# Module.net
KiCad netlist of a schematic drawn in Altium Designer
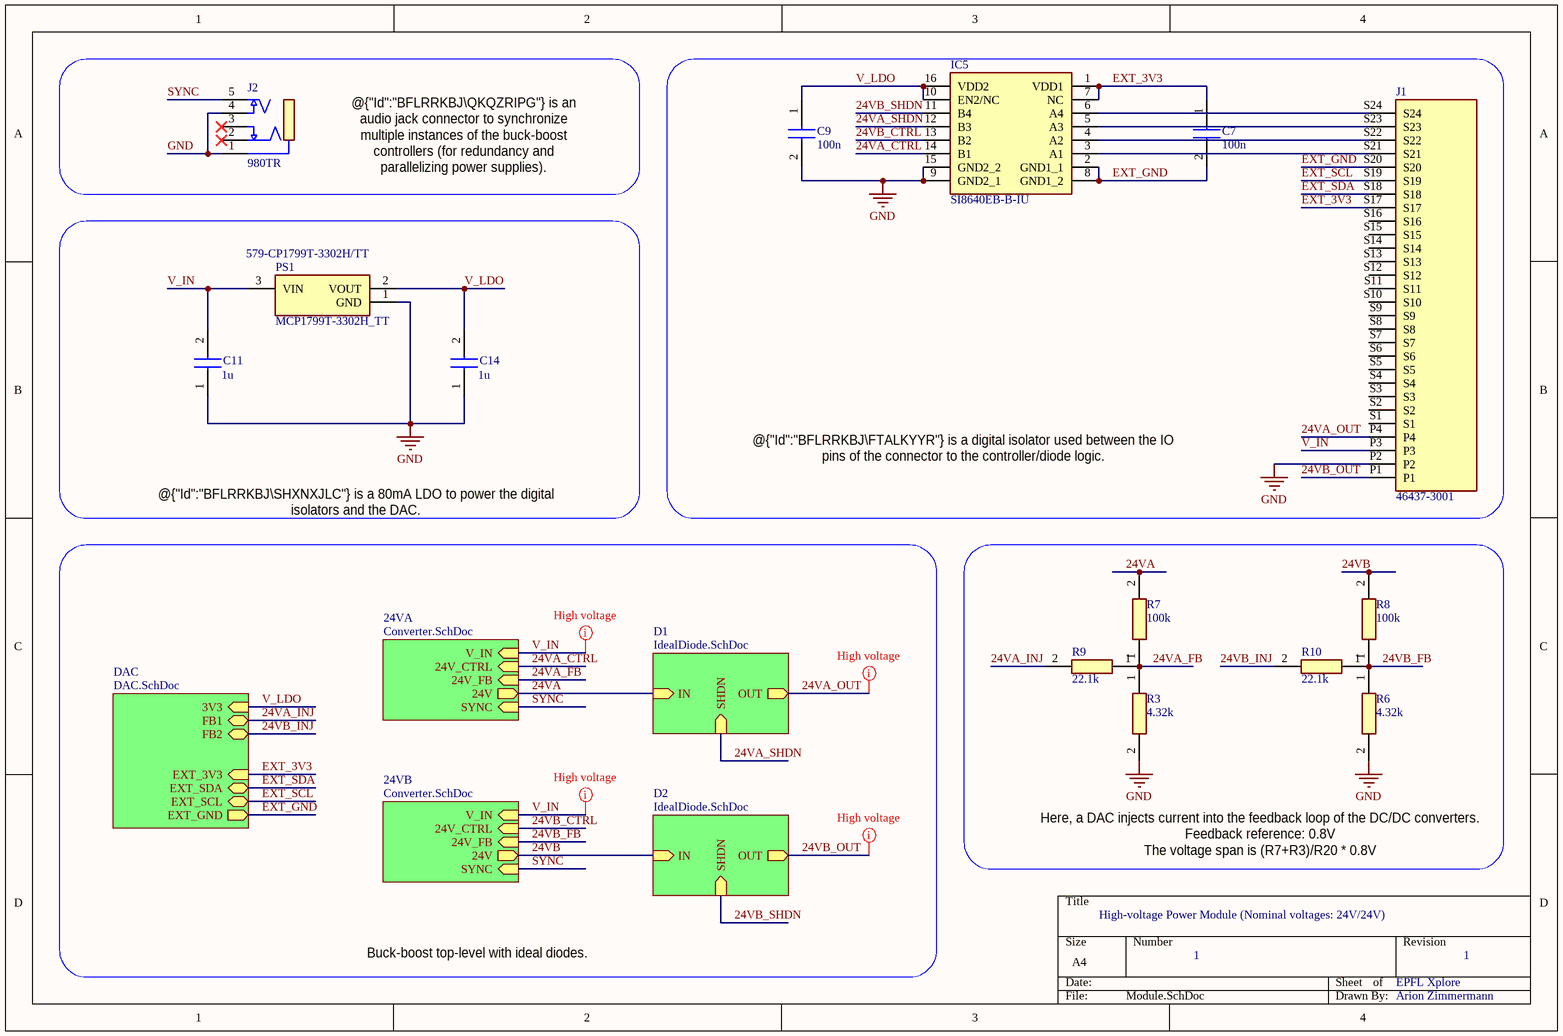
[diagram p0: Module.SchDoc]

(export (version "E")
  (design (tool "Eeschema 10.0.6"))
  (components
    (comp (ref "C7")
      (value "100n")
      (footprint "CAPC1608X95N")
      (description "Capacitor")
      (fields
        (field (name "MANUFACTURER_PART_NUMBER") "C0603C104K5RACTU")
        (field (name "MOUSER PART NUMBER") "80-C0603C104K5R")
      )
      (libsource (lib "*") (part "C0603C104K5RACTU"))
    )
    (comp (ref "C9")
      (value "100n")
      (footprint "CAPC1608X95N")
      (description "Capacitor")
      (fields
        (field (name "MANUFACTURER_PART_NUMBER") "C0603C104K5RACTU")
        (field (name "MOUSER PART NUMBER") "80-C0603C104K5R")
      )
      (libsource (lib "*") (part "C0603C104K5RACTU"))
    )
    (comp (ref "C11")
      (value "1u")
      (footprint "CAPC3216X110N")
      (description "Capacitor")
      (fields
        (field (name "MANUFACTURER_PART_NUMBER") "C1206C105K5RAC")
        (field (name "MOUSER PART NUMBER") "80-C1206C105K5RAC")
      )
      (libsource (lib "*") (part "C1206C105K5RAC"))
    )
    (comp (ref "C14")
      (value "1u")
      (footprint "CAPC3216X110N")
      (description "Capacitor")
      (fields
        (field (name "MANUFACTURER_PART_NUMBER") "C1206C105K5RAC")
        (field (name "MOUSER PART NUMBER") "80-C1206C105K5RAC")
      )
      (libsource (lib "*") (part "C1206C105K5RAC"))
    )
    (comp (ref "IC5")
      (value "SI8640EB-B-IU")
      (footprint "SamacSys:SOP64P600X175-16N")
      (description "Integrated Circuit")
      (fields (field (name "MOUSER PART NUMBER") "634-SI8640EB-B-IU"))
      (libsource (lib "*") (part "SI8640EB-B-IU"))
    )
    (comp (ref "J1")
      (value "46437-3001")
      (footprint "464373001")
      (description "Connector")
      (fields (field (name "MOUSER PART NUMBER") "538-46437-3001"))
      (libsource (lib "SamacSys") (part "46437-3001"))
    )
    (comp (ref "J2")
      (value "980TR")
      (footprint "SamacSys:980TR")
      (description "Connector")
      (fields (field (name "MOUSER PART NUMBER") "534-980"))
      (libsource (lib "*") (part "980TR"))
    )
    (comp (ref "PS1")
      (value "MCP1799T-3302H_TT")
      (footprint "SOT95P237X112-3N")
      (description "Power Supply")
      (fields
        (field (name "MANUFACTURER_PART_NUMBER") "MCP1799T-3302H/TT")
        (field (name "MOUSER PART NUMBER") "579-CP1799T-3302H/TT")
        (field (name "SUPPLIER PART NUMBER 1") "579-CP1799T-3302H/TT")
      )
      (libsource (lib "*") (part "MCP1799T-3302H_TT"))
    )
    (comp (ref "R3")
      (value "4.32k")
      (footprint "RESC1608X50N")
      (description "Resistor")
      (fields
        (field (name "MANUFACTURER_PART_NUMBER") "CRCW06034K32FKEA")
        (field (name "MOUSER PART NUMBER") "71-CRCW0603-4.32K-E3")
      )
      (libsource (lib "*") (part "CRCW06034K32FKEA"))
    )
    (comp (ref "R6")
      (value "4.32k")
      (footprint "RESC1608X50N")
      (description "Resistor")
      (fields
        (field (name "MANUFACTURER_PART_NUMBER") "CRCW06034K32FKEA")
        (field (name "MOUSER PART NUMBER") "71-CRCW0603-4.32K-E3")
      )
      (libsource (lib "*") (part "CRCW06034K32FKEA"))
    )
    (comp (ref "R7")
      (value "100k")
      (footprint "RESC1608X55N")
      (description "Resistor")
      (fields
        (field (name "MANUFACTURER_PART_NUMBER") "CRCW0603100KFKEAC")
        (field (name "MOUSER PART NUMBER") "71-CRCW0603100KFKEAC")
      )
      (libsource (lib "*") (part "CRCW0603100KFKEAC"))
    )
    (comp (ref "R8")
      (value "100k")
      (footprint "RESC1608X55N")
      (description "Resistor")
      (fields
        (field (name "MANUFACTURER_PART_NUMBER") "CRCW0603100KFKEAC")
        (field (name "MOUSER PART NUMBER") "71-CRCW0603100KFKEAC")
      )
      (libsource (lib "*") (part "CRCW0603100KFKEAC"))
    )
    (comp (ref "R9")
      (value "22.1k")
      (footprint "RESC1608X50N")
      (description "Resistor")
      (fields
        (field (name "MANUFACTURER_PART_NUMBER") "CRCW06037K50FKEB")
        (field (name "MOUSER PART NUMBER") "71-CRCW06037K50FKEB")
      )
      (libsource (lib "*") (part "CRCW06037K50FKEB"))
    )
    (comp (ref "R10")
      (value "22.1k")
      (footprint "RESC1608X50N")
      (description "Resistor")
      (fields
        (field (name "MANUFACTURER_PART_NUMBER") "CRCW06037K50FKEB")
        (field (name "MOUSER PART NUMBER") "71-CRCW06037K50FKEB")
      )
      (libsource (lib "*") (part "CRCW06037K50FKEB"))
    )
  )
  (nets
    (net (code "1") (name "/24VA") (class "Default")
      (node (ref "R7") (pin "2") (pinfunction "2_2") (pintype "passive"))
    )
    (net (code "2") (name "/24VA_CTRL") (class "Default")
      (node (ref "IC5") (pin "14") (pinfunction "B1_14") (pintype "passive"))
    )
    (net (code "3") (name "/24VA_FB") (class "Default")
      (node (ref "R3") (pin "1") (pinfunction "1_1") (pintype "passive"))
      (node (ref "R7") (pin "1") (pinfunction "1_1") (pintype "passive"))
      (node (ref "R9") (pin "1") (pinfunction "1_1") (pintype "passive"))
    )
    (net (code "4") (name "/24VA_INJ") (class "Default")
      (node (ref "R9") (pin "2") (pinfunction "2_2") (pintype "passive"))
    )
    (net (code "5") (name "/24VA_OUT") (class "Default")
      (node (ref "J1") (pin "P4") (pinfunction "P4_P4") (pintype "passive"))
    )
    (net (code "6") (name "/24VA_SHDN") (class "Default")
      (node (ref "IC5") (pin "12") (pinfunction "B3_12") (pintype "passive"))
    )
    (net (code "7") (name "/24VB") (class "Default")
      (node (ref "R8") (pin "2") (pinfunction "2_2") (pintype "passive"))
    )
    (net (code "8") (name "/24VB_CTRL") (class "Default")
      (node (ref "IC5") (pin "13") (pinfunction "B2_13") (pintype "passive"))
    )
    (net (code "9") (name "/24VB_FB") (class "Default")
      (node (ref "R10") (pin "1") (pinfunction "1_1") (pintype "passive"))
      (node (ref "R6") (pin "1") (pinfunction "1_1") (pintype "passive"))
      (node (ref "R8") (pin "1") (pinfunction "1_1") (pintype "passive"))
    )
    (net (code "10") (name "/24VB_INJ") (class "Default")
      (node (ref "R10") (pin "2") (pinfunction "2_2") (pintype "passive"))
    )
    (net (code "11") (name "/24VB_OUT") (class "Default")
      (node (ref "J1") (pin "P1") (pinfunction "P1_P1") (pintype "passive"))
    )
    (net (code "12") (name "/24VB_SHDN") (class "Default")
      (node (ref "IC5") (pin "11") (pinfunction "B4_11") (pintype "passive"))
    )
    (net (code "13") (name "/EXT_3V3") (class "Default")
      (node (ref "C7") (pin "1") (pinfunction "1_1") (pintype "passive"))
      (node (ref "IC5") (pin "1") (pinfunction "VDD1_1") (pintype "passive"))
      (node (ref "IC5") (pin "7") (pinfunction "NC_7") (pintype "passive"))
      (node (ref "J1") (pin "S17") (pinfunction "S17_S17") (pintype "passive"))
    )
    (net (code "14") (name "/EXT_GND") (class "Default")
      (node (ref "C7") (pin "2") (pinfunction "2_2") (pintype "passive"))
      (node (ref "IC5") (pin "2") (pinfunction "GND1_1_2") (pintype "passive"))
      (node (ref "IC5") (pin "8") (pinfunction "GND1_2_8") (pintype "passive"))
      (node (ref "J1") (pin "S20") (pinfunction "S20_S20") (pintype "passive"))
    )
    (net (code "15") (name "/EXT_SCL") (class "Default")
      (node (ref "J1") (pin "S19") (pinfunction "S19_S19") (pintype "passive"))
    )
    (net (code "16") (name "/EXT_SDA") (class "Default")
      (node (ref "J1") (pin "S18") (pinfunction "S18_S18") (pintype "passive"))
    )
    (net (code "17") (name "/SYNC") (class "Default")
      (node (ref "J2") (pin "5") (pinfunction "5_5") (pintype "passive"))
    )
    (net (code "18") (name "/V_IN") (class "Default")
      (node (ref "C11") (pin "2") (pinfunction "2_2") (pintype "passive"))
      (node (ref "J1") (pin "P3") (pinfunction "P3_P3") (pintype "passive"))
      (node (ref "PS1") (pin "3") (pinfunction "VIN_3") (pintype "passive"))
    )
    (net (code "19") (name "/V_LDO") (class "Default")
      (node (ref "C14") (pin "2") (pinfunction "2_2") (pintype "passive"))
      (node (ref "C9") (pin "1") (pinfunction "1_1") (pintype "passive"))
      (node (ref "IC5") (pin "10") (pinfunction "EN2/NC_10") (pintype "passive"))
      (node (ref "IC5") (pin "16") (pinfunction "VDD2_16") (pintype "passive"))
      (node (ref "PS1") (pin "2") (pinfunction "VOUT_2") (pintype "passive"))
    )
    (net (code "20") (name "GND") (class "Default")
      (node (ref "C11") (pin "1") (pinfunction "1_1") (pintype "passive"))
      (node (ref "C14") (pin "1") (pinfunction "1_1") (pintype "passive"))
      (node (ref "C9") (pin "2") (pinfunction "2_2") (pintype "passive"))
      (node (ref "IC5") (pin "15") (pinfunction "GND2_2_15") (pintype "passive"))
      (node (ref "IC5") (pin "9") (pinfunction "GND2_1_9") (pintype "passive"))
      (node (ref "J1") (pin "P2") (pinfunction "P2_P2") (pintype "passive"))
      (node (ref "J2") (pin "1") (pinfunction "1_1") (pintype "passive"))
      (node (ref "J2") (pin "4") (pinfunction "4_4") (pintype "passive"))
      (node (ref "PS1") (pin "1") (pinfunction "GND_1") (pintype "passive"))
      (node (ref "R3") (pin "2") (pinfunction "2_2") (pintype "passive"))
      (node (ref "R6") (pin "2") (pinfunction "2_2") (pintype "passive"))
    )
    (net (code "21") (name "Net-(IC5-A1)") (class "Default")
      (node (ref "IC5") (pin "3") (pinfunction "A1_3") (pintype "passive"))
      (node (ref "J1") (pin "S21") (pinfunction "S21_S21") (pintype "passive"))
    )
    (net (code "22") (name "Net-(IC5-A2)") (class "Default")
      (node (ref "IC5") (pin "4") (pinfunction "A2_4") (pintype "passive"))
      (node (ref "J1") (pin "S22") (pinfunction "S22_S22") (pintype "passive"))
    )
    (net (code "23") (name "Net-(IC5-A3)") (class "Default")
      (node (ref "IC5") (pin "5") (pinfunction "A3_5") (pintype "passive"))
      (node (ref "J1") (pin "S23") (pinfunction "S23_S23") (pintype "passive"))
    )
    (net (code "24") (name "Net-(IC5-A4)") (class "Default")
      (node (ref "IC5") (pin "6") (pinfunction "A4_6") (pintype "passive"))
      (node (ref "J1") (pin "S24") (pinfunction "S24_S24") (pintype "passive"))
    )
    (net (code "25") (name "unconnected-(J1-PadS1)") (class "Default")
      (node (ref "J1") (pin "S1") (pinfunction "S1_S1") (pintype "passive"))
    )
    (net (code "26") (name "unconnected-(J1-PadS2)") (class "Default")
      (node (ref "J1") (pin "S2") (pinfunction "S2_S2") (pintype "passive"))
    )
    (net (code "27") (name "unconnected-(J1-PadS3)") (class "Default")
      (node (ref "J1") (pin "S3") (pinfunction "S3_S3") (pintype "passive"))
    )
    (net (code "28") (name "unconnected-(J1-PadS4)") (class "Default")
      (node (ref "J1") (pin "S4") (pinfunction "S4_S4") (pintype "passive"))
    )
    (net (code "29") (name "unconnected-(J1-PadS5)") (class "Default")
      (node (ref "J1") (pin "S5") (pinfunction "S5_S5") (pintype "passive"))
    )
    (net (code "30") (name "unconnected-(J1-PadS6)") (class "Default")
      (node (ref "J1") (pin "S6") (pinfunction "S6_S6") (pintype "passive"))
    )
    (net (code "31") (name "unconnected-(J1-PadS7)") (class "Default")
      (node (ref "J1") (pin "S7") (pinfunction "S7_S7") (pintype "passive"))
    )
    (net (code "32") (name "unconnected-(J1-PadS8)") (class "Default")
      (node (ref "J1") (pin "S8") (pinfunction "S8_S8") (pintype "passive"))
    )
    (net (code "33") (name "unconnected-(J1-PadS9)") (class "Default")
      (node (ref "J1") (pin "S9") (pinfunction "S9_S9") (pintype "passive"))
    )
    (net (code "34") (name "unconnected-(J1-PadS10)") (class "Default")
      (node (ref "J1") (pin "S10") (pinfunction "S10_S10") (pintype "passive"))
    )
    (net (code "35") (name "unconnected-(J1-PadS11)") (class "Default")
      (node (ref "J1") (pin "S11") (pinfunction "S11_S11") (pintype "passive"))
    )
    (net (code "36") (name "unconnected-(J1-PadS12)") (class "Default")
      (node (ref "J1") (pin "S12") (pinfunction "S12_S12") (pintype "passive"))
    )
    (net (code "37") (name "unconnected-(J1-PadS13)") (class "Default")
      (node (ref "J1") (pin "S13") (pinfunction "S13_S13") (pintype "passive"))
    )
    (net (code "38") (name "unconnected-(J1-PadS14)") (class "Default")
      (node (ref "J1") (pin "S14") (pinfunction "S14_S14") (pintype "passive"))
    )
    (net (code "39") (name "unconnected-(J1-PadS15)") (class "Default")
      (node (ref "J1") (pin "S15") (pinfunction "S15_S15") (pintype "passive"))
    )
    (net (code "40") (name "unconnected-(J1-PadS16)") (class "Default")
      (node (ref "J1") (pin "S16") (pinfunction "S16_S16") (pintype "passive"))
    )
    (net (code "41") (name "unconnected-(J2-Pad2)") (class "Default")
      (node (ref "J2") (pin "2") (pinfunction "2_2") (pintype "passive+no_connect"))
    )
    (net (code "42") (name "unconnected-(J2-Pad3)") (class "Default")
      (node (ref "J2") (pin "3") (pinfunction "3_3") (pintype "passive+no_connect"))
    )
  )
)
